# SuperCapacitor_Schmatic_V3.net
KiCad netlist of a schematic drawn in EAGLE
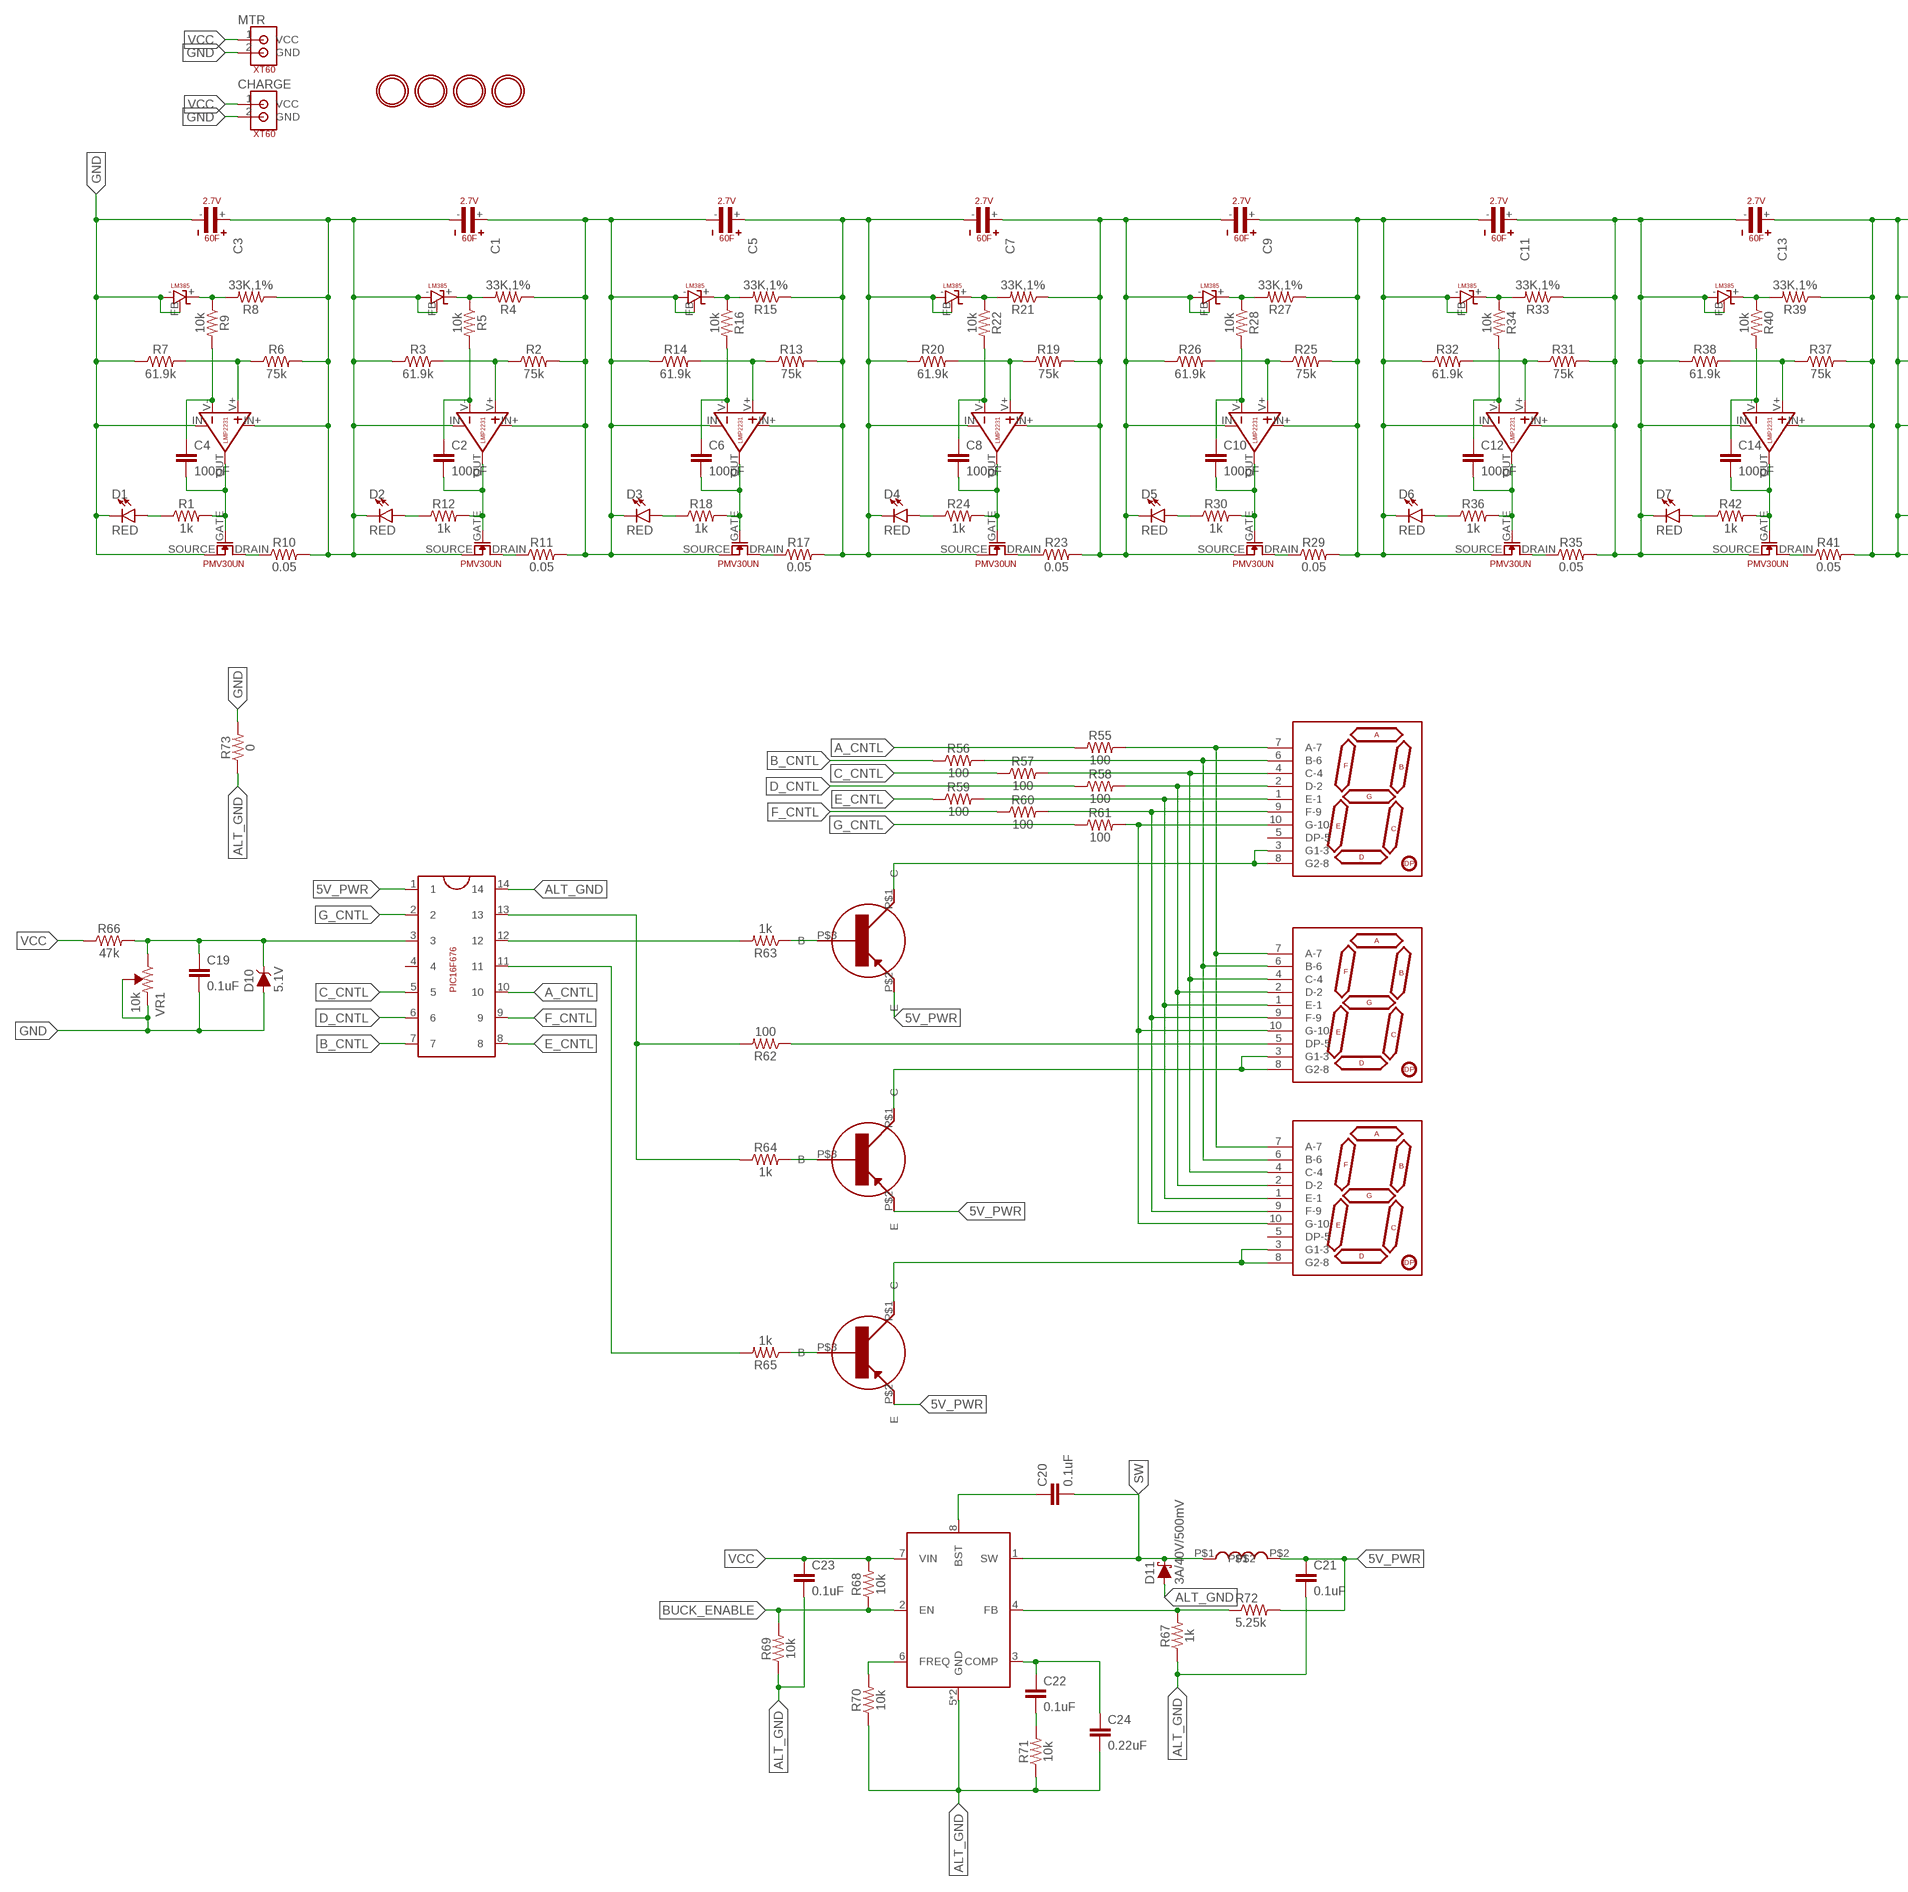
[diagram p0: schematic, sheet 1, part 1 of 2]
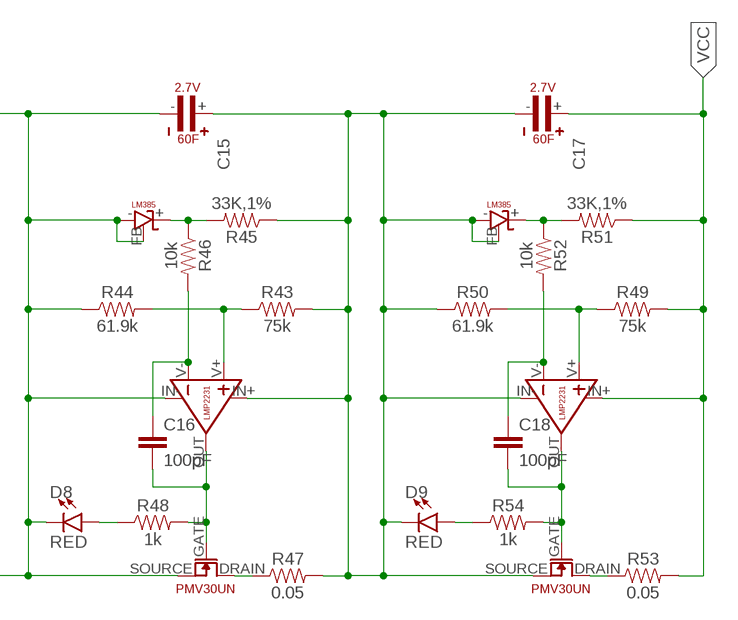
[diagram p1: schematic, sheet 1, part 2 of 2]

(export (version "E")
  (design (tool "Eeschema 10.0.6"))
  (components
    (comp (ref "3.3V_BUCK")
      (value "SOIC8E")
      (footprint "eagle-import:SOIC127P600X170-9N")
      (libsource (lib "eagle-import") (part "SOIC8E"))
    )
    (comp (ref "C1")
      (value "2.7V 60F")
      (footprint "eagle-import:2.7V_60F")
      (libsource (lib "eagle-import") (part "2.7V_60F"))
    )
    (comp (ref "C2")
      (value "100pF")
      (footprint "eagle-import:0603")
      (libsource (lib "eagle-import") (part "100PF-0603-50V-5%"))
    )
    (comp (ref "C3")
      (value "2.7V 60F")
      (footprint "eagle-import:2.7V_60F")
      (libsource (lib "eagle-import") (part "2.7V_60F"))
    )
    (comp (ref "C4")
      (value "100pF")
      (footprint "eagle-import:0603")
      (libsource (lib "eagle-import") (part "100PF-0603-50V-5%"))
    )
    (comp (ref "C5")
      (value "2.7V 60F")
      (footprint "eagle-import:2.7V_60F")
      (libsource (lib "eagle-import") (part "2.7V_60F"))
    )
    (comp (ref "C6")
      (value "100pF")
      (footprint "eagle-import:0603")
      (libsource (lib "eagle-import") (part "100PF-0603-50V-5%"))
    )
    (comp (ref "C7")
      (value "2.7V 60F")
      (footprint "eagle-import:2.7V_60F")
      (libsource (lib "eagle-import") (part "2.7V_60F"))
    )
    (comp (ref "C8")
      (value "100pF")
      (footprint "eagle-import:0603")
      (libsource (lib "eagle-import") (part "100PF-0603-50V-5%"))
    )
    (comp (ref "C9")
      (value "2.7V 60F")
      (footprint "eagle-import:2.7V_60F")
      (libsource (lib "eagle-import") (part "2.7V_60F"))
    )
    (comp (ref "C10")
      (value "100pF")
      (footprint "eagle-import:0603")
      (libsource (lib "eagle-import") (part "100PF-0603-50V-5%"))
    )
    (comp (ref "C11")
      (value "2.7V 60F")
      (footprint "eagle-import:2.7V_60F")
      (libsource (lib "eagle-import") (part "2.7V_60F"))
    )
    (comp (ref "C12")
      (value "100pF")
      (footprint "eagle-import:0603")
      (libsource (lib "eagle-import") (part "100PF-0603-50V-5%"))
    )
    (comp (ref "C13")
      (value "2.7V 60F")
      (footprint "eagle-import:2.7V_60F")
      (libsource (lib "eagle-import") (part "2.7V_60F"))
    )
    (comp (ref "C14")
      (value "100pF")
      (footprint "eagle-import:0603")
      (libsource (lib "eagle-import") (part "100PF-0603-50V-5%"))
    )
    (comp (ref "C15")
      (value "2.7V 60F")
      (footprint "eagle-import:2.7V_60F")
      (libsource (lib "eagle-import") (part "2.7V_60F"))
    )
    (comp (ref "C16")
      (value "100pF")
      (footprint "eagle-import:0603")
      (libsource (lib "eagle-import") (part "100PF-0603-50V-5%"))
    )
    (comp (ref "C17")
      (value "2.7V 60F")
      (footprint "eagle-import:2.7V_60F")
      (libsource (lib "eagle-import") (part "2.7V_60F"))
    )
    (comp (ref "C18")
      (value "100pF")
      (footprint "eagle-import:0603")
      (libsource (lib "eagle-import") (part "100PF-0603-50V-5%"))
    )
    (comp (ref "C19")
      (value "0.1uF")
      (footprint "eagle-import:0603")
      (libsource (lib "eagle-import") (part "SparkFun-Capacitors_510_0.1UF-0603-25V-5%"))
    )
    (comp (ref "C20")
      (value "0.1uF")
      (footprint "eagle-import:0603")
      (libsource (lib "eagle-import") (part "0.1UF-0603-25V-(+80/-20%)"))
    )
    (comp (ref "C21")
      (value "0.1uF")
      (footprint "eagle-import:0603")
      (libsource (lib "eagle-import") (part "0.1UF-0603-25V-(+80/-20%)"))
    )
    (comp (ref "C22")
      (value "0.1uF")
      (footprint "eagle-import:0603")
      (libsource (lib "eagle-import") (part "0.1UF-0603-25V-(+80/-20%)"))
    )
    (comp (ref "C23")
      (value "0.1uF")
      (footprint "eagle-import:0603")
      (libsource (lib "eagle-import") (part "0.1UF-0603-25V-(+80/-20%)"))
    )
    (comp (ref "C24")
      (value "0.22uF")
      (footprint "eagle-import:0603")
      (libsource (lib "eagle-import") (part "0.22UF-0603-50V-(-20/+80%)"))
    )
    (comp (ref "CHARGE")
      (value "XT60_CIRCLE")
      (footprint "eagle-import:XT60_CIRCLE")
      (libsource (lib "eagle-import") (part "XT60_CIRCLE"))
    )
    (comp (ref "D1")
      (value "RED")
      (footprint "eagle-import:LED-0603")
      (libsource (lib "eagle-import") (part "LED-RED0603"))
    )
    (comp (ref "D2")
      (value "RED")
      (footprint "eagle-import:LED-0603")
      (libsource (lib "eagle-import") (part "LED-RED0603"))
    )
    (comp (ref "D3")
      (value "RED")
      (footprint "eagle-import:LED-0603")
      (libsource (lib "eagle-import") (part "LED-RED0603"))
    )
    (comp (ref "D4")
      (value "RED")
      (footprint "eagle-import:LED-0603")
      (libsource (lib "eagle-import") (part "LED-RED0603"))
    )
    (comp (ref "D5")
      (value "RED")
      (footprint "eagle-import:LED-0603")
      (libsource (lib "eagle-import") (part "LED-RED0603"))
    )
    (comp (ref "D6")
      (value "RED")
      (footprint "eagle-import:LED-0603")
      (libsource (lib "eagle-import") (part "LED-RED0603"))
    )
    (comp (ref "D7")
      (value "RED")
      (footprint "eagle-import:LED-0603")
      (libsource (lib "eagle-import") (part "LED-RED0603"))
    )
    (comp (ref "D8")
      (value "RED")
      (footprint "eagle-import:LED-0603")
      (libsource (lib "eagle-import") (part "LED-RED0603"))
    )
    (comp (ref "D9")
      (value "RED")
      (footprint "eagle-import:LED-0603")
      (libsource (lib "eagle-import") (part "LED-RED0603"))
    )
    (comp (ref "D10")
      (value "5.1V")
      (footprint "eagle-import:SOD-323")
      (libsource (lib "eagle-import") (part "DIODE-ZENER-MMSZ5232BS"))
    )
    (comp (ref "D11")
      (value "3A/40V/500mV")
      (footprint "eagle-import:SMA-DIODE")
      (libsource (lib "eagle-import") (part "DIODE-SCHOTTKY-B340A"))
    )
    (comp (ref "MTR")
      (value "XT60_CIRCLE")
      (footprint "eagle-import:XT60_CIRCLE")
      (libsource (lib "eagle-import") (part "XT60_CIRCLE"))
    )
    (comp (ref "R1")
      (value "1k")
      (footprint "eagle-import:0603")
      (libsource (lib "eagle-import") (part "SparkFun-Resistors_532_1KOHM-0603-1/10W-1%"))
    )
    (comp (ref "R2")
      (value "75k")
      (footprint "eagle-import:0603@1")
      (libsource (lib "eagle-import") (part "75KOHM-0603-1/10W-1%"))
    )
    (comp (ref "R3")
      (value "61.9k")
      (footprint "eagle-import:0603@1")
      (libsource (lib "eagle-import") (part "75KOHM-0603-1/10W-1%"))
    )
    (comp (ref "R4")
      (value "33K,1%")
      (footprint "eagle-import:0603@1")
      (libsource (lib "eagle-import") (part "1MOHM-0603-1/4W-5%"))
    )
    (comp (ref "R5")
      (value "10k")
      (footprint "eagle-import:0603")
      (libsource (lib "eagle-import") (part "10KOHM-0603-1/10W-1%"))
    )
    (comp (ref "R6")
      (value "75k")
      (footprint "eagle-import:0603@1")
      (libsource (lib "eagle-import") (part "75KOHM-0603-1/10W-1%"))
    )
    (comp (ref "R7")
      (value "61.9k")
      (footprint "eagle-import:0603@1")
      (libsource (lib "eagle-import") (part "75KOHM-0603-1/10W-1%"))
    )
    (comp (ref "R8")
      (value "33K,1%")
      (footprint "eagle-import:0603@1")
      (libsource (lib "eagle-import") (part "1MOHM-0603-1/4W-5%"))
    )
    (comp (ref "R9")
      (value "10k")
      (footprint "eagle-import:0603")
      (libsource (lib "eagle-import") (part "10KOHM-0603-1/10W-1%"))
    )
    (comp (ref "R10")
      (value "0.05")
      (footprint "eagle-import:2512")
      (libsource (lib "eagle-import") (part "0.05OHM-2512-3W-1%"))
    )
    (comp (ref "R11")
      (value "0.05")
      (footprint "eagle-import:2512")
      (libsource (lib "eagle-import") (part "0.05OHM-2512-3W-1%"))
    )
    (comp (ref "R12")
      (value "1k")
      (footprint "eagle-import:0603")
      (libsource (lib "eagle-import") (part "SparkFun-Resistors_532_1KOHM-0603-1/10W-1%"))
    )
    (comp (ref "R13")
      (value "75k")
      (footprint "eagle-import:0603@1")
      (libsource (lib "eagle-import") (part "75KOHM-0603-1/10W-1%"))
    )
    (comp (ref "R14")
      (value "61.9k")
      (footprint "eagle-import:0603@1")
      (libsource (lib "eagle-import") (part "75KOHM-0603-1/10W-1%"))
    )
    (comp (ref "R15")
      (value "33K,1%")
      (footprint "eagle-import:0603@1")
      (libsource (lib "eagle-import") (part "1MOHM-0603-1/4W-5%"))
    )
    (comp (ref "R16")
      (value "10k")
      (footprint "eagle-import:0603")
      (libsource (lib "eagle-import") (part "10KOHM-0603-1/10W-1%"))
    )
    (comp (ref "R17")
      (value "0.05")
      (footprint "eagle-import:2512")
      (libsource (lib "eagle-import") (part "0.05OHM-2512-3W-1%"))
    )
    (comp (ref "R18")
      (value "1k")
      (footprint "eagle-import:0603")
      (libsource (lib "eagle-import") (part "SparkFun-Resistors_532_1KOHM-0603-1/10W-1%"))
    )
    (comp (ref "R19")
      (value "75k")
      (footprint "eagle-import:0603@1")
      (libsource (lib "eagle-import") (part "75KOHM-0603-1/10W-1%"))
    )
    (comp (ref "R20")
      (value "61.9k")
      (footprint "eagle-import:0603@1")
      (libsource (lib "eagle-import") (part "75KOHM-0603-1/10W-1%"))
    )
    (comp (ref "R21")
      (value "33K,1%")
      (footprint "eagle-import:0603@1")
      (libsource (lib "eagle-import") (part "1MOHM-0603-1/4W-5%"))
    )
    (comp (ref "R22")
      (value "10k")
      (footprint "eagle-import:0603")
      (libsource (lib "eagle-import") (part "10KOHM-0603-1/10W-1%"))
    )
    (comp (ref "R23")
      (value "0.05")
      (footprint "eagle-import:2512")
      (libsource (lib "eagle-import") (part "0.05OHM-2512-3W-1%"))
    )
    (comp (ref "R24")
      (value "1k")
      (footprint "eagle-import:0603")
      (libsource (lib "eagle-import") (part "SparkFun-Resistors_532_1KOHM-0603-1/10W-1%"))
    )
    (comp (ref "R25")
      (value "75k")
      (footprint "eagle-import:0603@1")
      (libsource (lib "eagle-import") (part "75KOHM-0603-1/10W-1%"))
    )
    (comp (ref "R26")
      (value "61.9k")
      (footprint "eagle-import:0603@1")
      (libsource (lib "eagle-import") (part "75KOHM-0603-1/10W-1%"))
    )
    (comp (ref "R27")
      (value "33K,1%")
      (footprint "eagle-import:0603@1")
      (libsource (lib "eagle-import") (part "1MOHM-0603-1/4W-5%"))
    )
    (comp (ref "R28")
      (value "10k")
      (footprint "eagle-import:0603")
      (libsource (lib "eagle-import") (part "10KOHM-0603-1/10W-1%"))
    )
    (comp (ref "R29")
      (value "0.05")
      (footprint "eagle-import:2512")
      (libsource (lib "eagle-import") (part "0.05OHM-2512-3W-1%"))
    )
    (comp (ref "R30")
      (value "1k")
      (footprint "eagle-import:0603")
      (libsource (lib "eagle-import") (part "SparkFun-Resistors_532_1KOHM-0603-1/10W-1%"))
    )
    (comp (ref "R31")
      (value "75k")
      (footprint "eagle-import:0603@1")
      (libsource (lib "eagle-import") (part "75KOHM-0603-1/10W-1%"))
    )
    (comp (ref "R32")
      (value "61.9k")
      (footprint "eagle-import:0603@1")
      (libsource (lib "eagle-import") (part "75KOHM-0603-1/10W-1%"))
    )
    (comp (ref "R33")
      (value "33K,1%")
      (footprint "eagle-import:0603@1")
      (libsource (lib "eagle-import") (part "1MOHM-0603-1/4W-5%"))
    )
    (comp (ref "R34")
      (value "10k")
      (footprint "eagle-import:0603")
      (libsource (lib "eagle-import") (part "10KOHM-0603-1/10W-1%"))
    )
    (comp (ref "R35")
      (value "0.05")
      (footprint "eagle-import:2512")
      (libsource (lib "eagle-import") (part "0.05OHM-2512-3W-1%"))
    )
    (comp (ref "R36")
      (value "1k")
      (footprint "eagle-import:0603")
      (libsource (lib "eagle-import") (part "SparkFun-Resistors_532_1KOHM-0603-1/10W-1%"))
    )
    (comp (ref "R37")
      (value "75k")
      (footprint "eagle-import:0603@1")
      (libsource (lib "eagle-import") (part "75KOHM-0603-1/10W-1%"))
    )
    (comp (ref "R38")
      (value "61.9k")
      (footprint "eagle-import:0603@1")
      (libsource (lib "eagle-import") (part "75KOHM-0603-1/10W-1%"))
    )
    (comp (ref "R39")
      (value "33K,1%")
      (footprint "eagle-import:0603@1")
      (libsource (lib "eagle-import") (part "1MOHM-0603-1/4W-5%"))
    )
    (comp (ref "R40")
      (value "10k")
      (footprint "eagle-import:0603")
      (libsource (lib "eagle-import") (part "10KOHM-0603-1/10W-1%"))
    )
    (comp (ref "R41")
      (value "0.05")
      (footprint "eagle-import:2512")
      (libsource (lib "eagle-import") (part "0.05OHM-2512-3W-1%"))
    )
    (comp (ref "R42")
      (value "1k")
      (footprint "eagle-import:0603")
      (libsource (lib "eagle-import") (part "SparkFun-Resistors_532_1KOHM-0603-1/10W-1%"))
    )
    (comp (ref "R43")
      (value "75k")
      (footprint "eagle-import:0603@1")
      (libsource (lib "eagle-import") (part "75KOHM-0603-1/10W-1%"))
    )
    (comp (ref "R44")
      (value "61.9k")
      (footprint "eagle-import:0603@1")
      (libsource (lib "eagle-import") (part "75KOHM-0603-1/10W-1%"))
    )
    (comp (ref "R45")
      (value "33K,1%")
      (footprint "eagle-import:0603@1")
      (libsource (lib "eagle-import") (part "1MOHM-0603-1/4W-5%"))
    )
    (comp (ref "R46")
      (value "10k")
      (footprint "eagle-import:0603")
      (libsource (lib "eagle-import") (part "10KOHM-0603-1/10W-1%"))
    )
    (comp (ref "R47")
      (value "0.05")
      (footprint "eagle-import:2512")
      (libsource (lib "eagle-import") (part "0.05OHM-2512-3W-1%"))
    )
    (comp (ref "R48")
      (value "1k")
      (footprint "eagle-import:0603")
      (libsource (lib "eagle-import") (part "SparkFun-Resistors_532_1KOHM-0603-1/10W-1%"))
    )
    (comp (ref "R49")
      (value "75k")
      (footprint "eagle-import:0603@1")
      (libsource (lib "eagle-import") (part "75KOHM-0603-1/10W-1%"))
    )
    (comp (ref "R50")
      (value "61.9k")
      (footprint "eagle-import:0603@1")
      (libsource (lib "eagle-import") (part "75KOHM-0603-1/10W-1%"))
    )
    (comp (ref "R51")
      (value "33K,1%")
      (footprint "eagle-import:0603@1")
      (libsource (lib "eagle-import") (part "1MOHM-0603-1/4W-5%"))
    )
    (comp (ref "R52")
      (value "10k")
      (footprint "eagle-import:0603")
      (libsource (lib "eagle-import") (part "10KOHM-0603-1/10W-1%"))
    )
    (comp (ref "R53")
      (value "0.05")
      (footprint "eagle-import:2512")
      (libsource (lib "eagle-import") (part "0.05OHM-2512-3W-1%"))
    )
    (comp (ref "R54")
      (value "1k")
      (footprint "eagle-import:0603")
      (libsource (lib "eagle-import") (part "SparkFun-Resistors_532_1KOHM-0603-1/10W-1%"))
    )
    (comp (ref "R55")
      (value "100")
      (footprint "eagle-import:0603")
      (libsource (lib "eagle-import") (part "100OHM-0603-1/4W-5%"))
    )
    (comp (ref "R56")
      (value "100")
      (footprint "eagle-import:0603")
      (libsource (lib "eagle-import") (part "100OHM-0603-1/4W-5%"))
    )
    (comp (ref "R57")
      (value "100")
      (footprint "eagle-import:0603")
      (libsource (lib "eagle-import") (part "100OHM-0603-1/4W-5%"))
    )
    (comp (ref "R58")
      (value "100")
      (footprint "eagle-import:0603")
      (libsource (lib "eagle-import") (part "100OHM-0603-1/4W-5%"))
    )
    (comp (ref "R59")
      (value "100")
      (footprint "eagle-import:0603")
      (libsource (lib "eagle-import") (part "100OHM-0603-1/4W-5%"))
    )
    (comp (ref "R60")
      (value "100")
      (footprint "eagle-import:0603")
      (libsource (lib "eagle-import") (part "100OHM-0603-1/4W-5%"))
    )
    (comp (ref "R61")
      (value "100")
      (footprint "eagle-import:0603")
      (libsource (lib "eagle-import") (part "100OHM-0603-1/4W-5%"))
    )
    (comp (ref "R62")
      (value "100")
      (footprint "eagle-import:0603")
      (libsource (lib "eagle-import") (part "100OHM-0603-1/4W-5%"))
    )
    (comp (ref "R63")
      (value "1k")
      (footprint "eagle-import:0603")
      (libsource (lib "eagle-import") (part "SparkFun-Resistors_532_1KOHM-0603-1/10W-1%"))
    )
    (comp (ref "R64")
      (value "1k")
      (footprint "eagle-import:0603")
      (libsource (lib "eagle-import") (part "SparkFun-Resistors_532_1KOHM-0603-1/10W-1%"))
    )
    (comp (ref "R65")
      (value "1k")
      (footprint "eagle-import:0603")
      (libsource (lib "eagle-import") (part "SparkFun-Resistors_532_1KOHM-0603-1/10W-1%"))
    )
    (comp (ref "R66")
      (value "47k")
      (footprint "eagle-import:0603")
      (libsource (lib "eagle-import") (part "47KOHM-0603-1/10W-1%"))
    )
    (comp (ref "R67")
      (value "1k")
      (footprint "eagle-import:0603")
      (libsource (lib "eagle-import") (part "1KOHM-0603-1/10W-1%"))
    )
    (comp (ref "R68")
      (value "10k")
      (footprint "eagle-import:0603")
      (libsource (lib "eagle-import") (part "10KOHM-0603-1/10W-1%"))
    )
    (comp (ref "R69")
      (value "10k")
      (footprint "eagle-import:0603")
      (libsource (lib "eagle-import") (part "10KOHM-0603-1/10W-1%"))
    )
    (comp (ref "R70")
      (value "10k")
      (footprint "eagle-import:0603")
      (libsource (lib "eagle-import") (part "10KOHM-0603-1/10W-1%"))
    )
    (comp (ref "R71")
      (value "10k")
      (footprint "eagle-import:0603")
      (libsource (lib "eagle-import") (part "10KOHM-0603-1/10W-1%"))
    )
    (comp (ref "R72")
      (value "5.25k")
      (footprint "eagle-import:RES_0805")
      (fields
        (field (name "DIGIKEY_PART_NUMBER") "541-0.0ATR-ND")
        (field (name "MANUFACTURER") "Vishay Dale")
        (field (name "MPN") "CRCW08050000Z0EA")
        (field (name "CREATED_BY") "PCBLayout.com")
      )
      (libsource (lib "eagle-import") (part "CRCW08050000Z0EA"))
    )
    (comp (ref "R73")
      (value "0")
      (footprint "eagle-import:0603")
      (libsource (lib "eagle-import") (part "0OHM-0603-1/10W-5%"))
    )
    (comp (ref "U$1")
      (value "LMP2231")
      (footprint "eagle-import:LMP2231_SOT23_5")
      (libsource (lib "eagle-import") (part "LMP2231"))
    )
    (comp (ref "U$2")
      (value "LM385")
      (footprint "eagle-import:LM385_SOT23")
      (libsource (lib "eagle-import") (part "LM385"))
    )
    (comp (ref "U$3")
      (value "PMV30UN_MOS")
      (footprint "eagle-import:PMV30UN_SOT23")
      (libsource (lib "eagle-import") (part "PMV30UN_MOS"))
    )
    (comp (ref "U$4")
      (value "LMP2231")
      (footprint "eagle-import:LMP2231_SOT23_5")
      (libsource (lib "eagle-import") (part "LMP2231"))
    )
    (comp (ref "U$5")
      (value "LM385")
      (footprint "eagle-import:LM385_SOT23")
      (libsource (lib "eagle-import") (part "LM385"))
    )
    (comp (ref "U$6")
      (value "PMV30UN_MOS")
      (footprint "eagle-import:PMV30UN_SOT23")
      (libsource (lib "eagle-import") (part "PMV30UN_MOS"))
    )
    (comp (ref "U$7")
      (value "LMP2231")
      (footprint "eagle-import:LMP2231_SOT23_5")
      (libsource (lib "eagle-import") (part "LMP2231"))
    )
    (comp (ref "U$8")
      (value "LM385")
      (footprint "eagle-import:LM385_SOT23")
      (libsource (lib "eagle-import") (part "LM385"))
    )
    (comp (ref "U$9")
      (value "PMV30UN_MOS")
      (footprint "eagle-import:PMV30UN_SOT23")
      (libsource (lib "eagle-import") (part "PMV30UN_MOS"))
    )
    (comp (ref "U$10")
      (value "LMP2231")
      (footprint "eagle-import:LMP2231_SOT23_5")
      (libsource (lib "eagle-import") (part "LMP2231"))
    )
    (comp (ref "U$11")
      (value "LM385")
      (footprint "eagle-import:LM385_SOT23")
      (libsource (lib "eagle-import") (part "LM385"))
    )
    (comp (ref "U$12")
      (value "PMV30UN_MOS")
      (footprint "eagle-import:PMV30UN_SOT23")
      (libsource (lib "eagle-import") (part "PMV30UN_MOS"))
    )
    (comp (ref "U$13")
      (value "LMP2231")
      (footprint "eagle-import:LMP2231_SOT23_5")
      (libsource (lib "eagle-import") (part "LMP2231"))
    )
    (comp (ref "U$14")
      (value "LM385")
      (footprint "eagle-import:LM385_SOT23")
      (libsource (lib "eagle-import") (part "LM385"))
    )
    (comp (ref "U$15")
      (value "PMV30UN_MOS")
      (footprint "eagle-import:PMV30UN_SOT23")
      (libsource (lib "eagle-import") (part "PMV30UN_MOS"))
    )
    (comp (ref "U$16")
      (value "LMP2231")
      (footprint "eagle-import:LMP2231_SOT23_5")
      (libsource (lib "eagle-import") (part "LMP2231"))
    )
    (comp (ref "U$17")
      (value "LM385")
      (footprint "eagle-import:LM385_SOT23")
      (libsource (lib "eagle-import") (part "LM385"))
    )
    (comp (ref "U$18")
      (value "PMV30UN_MOS")
      (footprint "eagle-import:PMV30UN_SOT23")
      (libsource (lib "eagle-import") (part "PMV30UN_MOS"))
    )
    (comp (ref "U$19")
      (value "LMP2231")
      (footprint "eagle-import:LMP2231_SOT23_5")
      (libsource (lib "eagle-import") (part "LMP2231"))
    )
    (comp (ref "U$20")
      (value "LM385")
      (footprint "eagle-import:LM385_SOT23")
      (libsource (lib "eagle-import") (part "LM385"))
    )
    (comp (ref "U$21")
      (value "PMV30UN_MOS")
      (footprint "eagle-import:PMV30UN_SOT23")
      (libsource (lib "eagle-import") (part "PMV30UN_MOS"))
    )
    (comp (ref "U$22")
      (value "LMP2231")
      (footprint "eagle-import:LMP2231_SOT23_5")
      (libsource (lib "eagle-import") (part "LMP2231"))
    )
    (comp (ref "U$23")
      (value "LM385")
      (footprint "eagle-import:LM385_SOT23")
      (libsource (lib "eagle-import") (part "LM385"))
    )
    (comp (ref "U$24")
      (value "PMV30UN_MOS")
      (footprint "eagle-import:PMV30UN_SOT23")
      (libsource (lib "eagle-import") (part "PMV30UN_MOS"))
    )
    (comp (ref "U$25")
      (value "LMP2231")
      (footprint "eagle-import:LMP2231_SOT23_5")
      (libsource (lib "eagle-import") (part "LMP2231"))
    )
    (comp (ref "U$26")
      (value "LM385")
      (footprint "eagle-import:LM385_SOT23")
      (libsource (lib "eagle-import") (part "LM385"))
    )
    (comp (ref "U$27")
      (value "PMV30UN_MOS")
      (footprint "eagle-import:PMV30UN_SOT23")
      (libsource (lib "eagle-import") (part "PMV30UN_MOS"))
    )
    (comp (ref "U$30")
      (value "M5")
      (footprint "eagle-import:M5")
      (libsource (lib "eagle-import") (part "M5"))
    )
    (comp (ref "U$31")
      (value "M5")
      (footprint "eagle-import:M5")
      (libsource (lib "eagle-import") (part "M5"))
    )
    (comp (ref "U$32")
      (value "M5")
      (footprint "eagle-import:M5")
      (libsource (lib "eagle-import") (part "M5"))
    )
    (comp (ref "U$33")
      (value "M5")
      (footprint "eagle-import:M5")
      (libsource (lib "eagle-import") (part "M5"))
    )
    (comp (ref "U$35")
      (value "DSM7T")
      (footprint "eagle-import:7-SEGMENT_SMD")
      (libsource (lib "eagle-import") (part "DSM7T"))
    )
    (comp (ref "U$36")
      (value "DSM7T")
      (footprint "eagle-import:7-SEGMENT_SMD")
      (libsource (lib "eagle-import") (part "DSM7T"))
    )
    (comp (ref "U$37")
      (value "DSM7T")
      (footprint "eagle-import:7-SEGMENT_SMD")
      (libsource (lib "eagle-import") (part "DSM7T"))
    )
    (comp (ref "U$38")
      (value "PIC16F676")
      (footprint "eagle-import:PIC16F676")
      (libsource (lib "eagle-import") (part "PIC16F676"))
    )
    (comp (ref "U$39")
      (value "4.7UH_INDUCTOR")
      (footprint "eagle-import:4.7UH_INDUCTOR")
      (libsource (lib "eagle-import") (part "4.7UH_INDUCTOR"))
    )
    (comp (ref "U$40")
      (value "SOT_223")
      (footprint "eagle-import:BC856BMB")
      (libsource (lib "eagle-import") (part "SOT_223"))
    )
    (comp (ref "U$41")
      (value "SOT_223")
      (footprint "eagle-import:BC856BMB")
      (libsource (lib "eagle-import") (part "SOT_223"))
    )
    (comp (ref "U$42")
      (value "SOT_223")
      (footprint "eagle-import:BC856BMB")
      (libsource (lib "eagle-import") (part "SOT_223"))
    )
    (comp (ref "VR1")
      (value "10k")
      (footprint "eagle-import:TRIMPOT-SMD-TC33X")
      (libsource (lib "eagle-import") (part "TRIMPOT-SMD-3MM-OPEN-1/10W-25%"))
    )
  )
  (nets
    (net (code "1") (name "5V_PWR") (class "Default")
      (node (ref "C21") (pin "1") (pinfunction "1_1") (pintype "passive"))
      (node (ref "R72") (pin "2") (pinfunction "2_2") (pintype "passive"))
      (node (ref "U$38") (pin "1") (pinfunction "1_1") (pintype "bidirectional"))
      (node (ref "U$39") (pin "P$2") (pinfunction "P$2_P$2") (pintype "bidirectional"))
      (node (ref "U$40") (pin "P$2") (pinfunction "E_P$2") (pintype "bidirectional"))
      (node (ref "U$41") (pin "P$2") (pinfunction "E_P$2") (pintype "bidirectional"))
      (node (ref "U$42") (pin "P$2") (pinfunction "E_P$2") (pintype "bidirectional"))
    )
    (net (code "2") (name "ALT_GND") (class "Default")
      (node (ref "3.3V_BUCK") (pin "5") (pinfunction "GND_5") (pintype "bidirectional"))
      (node (ref "3.3V_BUCK") (pin "9") (pinfunction "GND_9") (pintype "bidirectional"))
      (node (ref "C21") (pin "2") (pinfunction "2_2") (pintype "passive"))
      (node (ref "C23") (pin "2") (pinfunction "2_2") (pintype "passive"))
      (node (ref "C24") (pin "2") (pinfunction "2_2") (pintype "passive"))
      (node (ref "D11") (pin "A") (pinfunction "A_A") (pintype "passive"))
      (node (ref "R67") (pin "1") (pinfunction "1_1") (pintype "passive"))
      (node (ref "R69") (pin "1") (pinfunction "1_1") (pintype "passive"))
      (node (ref "R70") (pin "1") (pinfunction "1_1") (pintype "passive"))
      (node (ref "R71") (pin "1") (pinfunction "1_1") (pintype "passive"))
      (node (ref "R73") (pin "1") (pinfunction "1_1") (pintype "passive"))
      (node (ref "U$38") (pin "14") (pinfunction "14_14") (pintype "bidirectional"))
    )
    (net (code "3") (name "A_CNTL") (class "Default")
      (node (ref "R55") (pin "1") (pinfunction "1_1") (pintype "passive"))
      (node (ref "U$38") (pin "10") (pinfunction "10_10") (pintype "bidirectional"))
    )
    (net (code "4") (name "BUCK_ENABLE") (class "Default")
      (node (ref "3.3V_BUCK") (pin "2") (pinfunction "EN_2") (pintype "bidirectional"))
      (node (ref "R68") (pin "1") (pinfunction "1_1") (pintype "passive"))
      (node (ref "R69") (pin "2") (pinfunction "2_2") (pintype "passive"))
    )
    (net (code "5") (name "B_CNTL") (class "Default")
      (node (ref "R56") (pin "1") (pinfunction "1_1") (pintype "passive"))
      (node (ref "U$38") (pin "7") (pinfunction "7_7") (pintype "bidirectional"))
    )
    (net (code "6") (name "C_CNTL") (class "Default")
      (node (ref "R57") (pin "1") (pinfunction "1_1") (pintype "passive"))
      (node (ref "U$38") (pin "5") (pinfunction "5_5") (pintype "bidirectional"))
    )
    (net (code "7") (name "D_CNTL") (class "Default")
      (node (ref "R58") (pin "1") (pinfunction "1_1") (pintype "passive"))
      (node (ref "U$38") (pin "6") (pinfunction "6_6") (pintype "bidirectional"))
    )
    (net (code "8") (name "E_CNTL") (class "Default")
      (node (ref "R59") (pin "1") (pinfunction "1_1") (pintype "passive"))
      (node (ref "U$38") (pin "8") (pinfunction "8_8") (pintype "bidirectional"))
    )
    (net (code "9") (name "F_CNTL") (class "Default")
      (node (ref "R60") (pin "1") (pinfunction "1_1") (pintype "passive"))
      (node (ref "U$38") (pin "9") (pinfunction "9_9") (pintype "bidirectional"))
    )
    (net (code "10") (name "GND") (class "Default")
      (node (ref "C19") (pin "2") (pinfunction "2_2") (pintype "passive"))
      (node (ref "C3") (pin "-") (pinfunction "-_-") (pintype "bidirectional"))
      (node (ref "CHARGE") (pin "2") (pinfunction "GND_2") (pintype "bidirectional"))
      (node (ref "D1") (pin "C") (pinfunction "C_C") (pintype "passive"))
      (node (ref "D10") (pin "A") (pinfunction "A_A") (pintype "passive"))
      (node (ref "MTR") (pin "2") (pinfunction "GND_2") (pintype "bidirectional"))
      (node (ref "R7") (pin "1") (pinfunction "1_1") (pintype "passive"))
      (node (ref "R73") (pin "2") (pinfunction "2_2") (pintype "passive"))
      (node (ref "U$4") (pin "IN-") (pinfunction "IN-_IN-") (pintype "bidirectional"))
      (node (ref "U$5") (pin "-") (pinfunction "-_-") (pintype "bidirectional"))
      (node (ref "U$5") (pin "FB") (pinfunction "FB_FB") (pintype "bidirectional"))
      (node (ref "U$6") (pin "SOURCE") (pinfunction "SOURCE_SOURCE") (pintype "bidirectional"))
      (node (ref "VR1") (pin "2") (pinfunction "WIPER_2") (pintype "passive"))
      (node (ref "VR1") (pin "3") (pinfunction "CCW_3") (pintype "passive"))
    )
    (net (code "11") (name "G_CNTL") (class "Default")
      (node (ref "R61") (pin "1") (pinfunction "1_1") (pintype "passive"))
      (node (ref "U$38") (pin "2") (pinfunction "2_2") (pintype "bidirectional"))
    )
    (net (code "12") (name "Net-(3.3V_BUCK-BST)") (class "Default")
      (node (ref "3.3V_BUCK") (pin "8") (pinfunction "BST_8") (pintype "bidirectional"))
      (node (ref "C20") (pin "1") (pinfunction "1_1") (pintype "passive"))
    )
    (net (code "13") (name "Net-(3.3V_BUCK-COMP)") (class "Default")
      (node (ref "3.3V_BUCK") (pin "3") (pinfunction "COMP_3") (pintype "bidirectional"))
      (node (ref "C22") (pin "1") (pinfunction "1_1") (pintype "passive"))
      (node (ref "C24") (pin "1") (pinfunction "1_1") (pintype "passive"))
    )
    (net (code "14") (name "Net-(3.3V_BUCK-FB)") (class "Default")
      (node (ref "3.3V_BUCK") (pin "4") (pinfunction "FB_4") (pintype "bidirectional"))
      (node (ref "R67") (pin "2") (pinfunction "2_2") (pintype "passive"))
      (node (ref "R72") (pin "1") (pinfunction "1_1") (pintype "passive"))
    )
    (net (code "15") (name "Net-(3.3V_BUCK-FREQ)") (class "Default")
      (node (ref "3.3V_BUCK") (pin "6") (pinfunction "FREQ_6") (pintype "bidirectional"))
      (node (ref "R70") (pin "2") (pinfunction "2_2") (pintype "passive"))
    )
    (net (code "16") (name "Net-(C2-Pad1)") (class "Default")
      (node (ref "C2") (pin "1") (pinfunction "1_1") (pintype "passive"))
      (node (ref "R5") (pin "2") (pinfunction "2_2") (pintype "passive"))
      (node (ref "U$1") (pin "V-") (pinfunction "V-_V-") (pintype "bidirectional"))
    )
    (net (code "17") (name "Net-(C2-Pad2)") (class "Default")
      (node (ref "C2") (pin "2") (pinfunction "2_2") (pintype "passive"))
      (node (ref "R12") (pin "2") (pinfunction "2_2") (pintype "passive"))
      (node (ref "U$1") (pin "OUT") (pinfunction "OUT_OUT") (pintype "bidirectional"))
      (node (ref "U$3") (pin "GATE") (pinfunction "GATE_GATE") (pintype "bidirectional"))
    )
    (net (code "18") (name "Net-(C4-Pad1)") (class "Default")
      (node (ref "C4") (pin "1") (pinfunction "1_1") (pintype "passive"))
      (node (ref "R9") (pin "2") (pinfunction "2_2") (pintype "passive"))
      (node (ref "U$4") (pin "V-") (pinfunction "V-_V-") (pintype "bidirectional"))
    )
    (net (code "19") (name "Net-(C4-Pad2)") (class "Default")
      (node (ref "C4") (pin "2") (pinfunction "2_2") (pintype "passive"))
      (node (ref "R1") (pin "2") (pinfunction "2_2") (pintype "passive"))
      (node (ref "U$4") (pin "OUT") (pinfunction "OUT_OUT") (pintype "bidirectional"))
      (node (ref "U$6") (pin "GATE") (pinfunction "GATE_GATE") (pintype "bidirectional"))
    )
    (net (code "20") (name "Net-(C6-Pad1)") (class "Default")
      (node (ref "C6") (pin "1") (pinfunction "1_1") (pintype "passive"))
      (node (ref "R16") (pin "2") (pinfunction "2_2") (pintype "passive"))
      (node (ref "U$7") (pin "V-") (pinfunction "V-_V-") (pintype "bidirectional"))
    )
    (net (code "21") (name "Net-(C6-Pad2)") (class "Default")
      (node (ref "C6") (pin "2") (pinfunction "2_2") (pintype "passive"))
      (node (ref "R18") (pin "2") (pinfunction "2_2") (pintype "passive"))
      (node (ref "U$7") (pin "OUT") (pinfunction "OUT_OUT") (pintype "bidirectional"))
      (node (ref "U$9") (pin "GATE") (pinfunction "GATE_GATE") (pintype "bidirectional"))
    )
    (net (code "22") (name "Net-(C8-Pad1)") (class "Default")
      (node (ref "C8") (pin "1") (pinfunction "1_1") (pintype "passive"))
      (node (ref "R22") (pin "2") (pinfunction "2_2") (pintype "passive"))
      (node (ref "U$10") (pin "V-") (pinfunction "V-_V-") (pintype "bidirectional"))
    )
    (net (code "23") (name "Net-(C8-Pad2)") (class "Default")
      (node (ref "C8") (pin "2") (pinfunction "2_2") (pintype "passive"))
      (node (ref "R24") (pin "2") (pinfunction "2_2") (pintype "passive"))
      (node (ref "U$10") (pin "OUT") (pinfunction "OUT_OUT") (pintype "bidirectional"))
      (node (ref "U$12") (pin "GATE") (pinfunction "GATE_GATE") (pintype "bidirectional"))
    )
    (net (code "24") (name "Net-(C10-Pad1)") (class "Default")
      (node (ref "C10") (pin "1") (pinfunction "1_1") (pintype "passive"))
      (node (ref "R28") (pin "2") (pinfunction "2_2") (pintype "passive"))
      (node (ref "U$13") (pin "V-") (pinfunction "V-_V-") (pintype "bidirectional"))
    )
    (net (code "25") (name "Net-(C10-Pad2)") (class "Default")
      (node (ref "C10") (pin "2") (pinfunction "2_2") (pintype "passive"))
      (node (ref "R30") (pin "2") (pinfunction "2_2") (pintype "passive"))
      (node (ref "U$13") (pin "OUT") (pinfunction "OUT_OUT") (pintype "bidirectional"))
      (node (ref "U$15") (pin "GATE") (pinfunction "GATE_GATE") (pintype "bidirectional"))
    )
    (net (code "26") (name "Net-(C12-Pad1)") (class "Default")
      (node (ref "C12") (pin "1") (pinfunction "1_1") (pintype "passive"))
      (node (ref "R34") (pin "2") (pinfunction "2_2") (pintype "passive"))
      (node (ref "U$16") (pin "V-") (pinfunction "V-_V-") (pintype "bidirectional"))
    )
    (net (code "27") (name "Net-(C12-Pad2)") (class "Default")
      (node (ref "C12") (pin "2") (pinfunction "2_2") (pintype "passive"))
      (node (ref "R36") (pin "2") (pinfunction "2_2") (pintype "passive"))
      (node (ref "U$16") (pin "OUT") (pinfunction "OUT_OUT") (pintype "bidirectional"))
      (node (ref "U$18") (pin "GATE") (pinfunction "GATE_GATE") (pintype "bidirectional"))
    )
    (net (code "28") (name "Net-(C14-Pad1)") (class "Default")
      (node (ref "C14") (pin "1") (pinfunction "1_1") (pintype "passive"))
      (node (ref "R40") (pin "2") (pinfunction "2_2") (pintype "passive"))
      (node (ref "U$19") (pin "V-") (pinfunction "V-_V-") (pintype "bidirectional"))
    )
    (net (code "29") (name "Net-(C14-Pad2)") (class "Default")
      (node (ref "C14") (pin "2") (pinfunction "2_2") (pintype "passive"))
      (node (ref "R42") (pin "2") (pinfunction "2_2") (pintype "passive"))
      (node (ref "U$19") (pin "OUT") (pinfunction "OUT_OUT") (pintype "bidirectional"))
      (node (ref "U$21") (pin "GATE") (pinfunction "GATE_GATE") (pintype "bidirectional"))
    )
    (net (code "30") (name "Net-(C16-Pad1)") (class "Default")
      (node (ref "C16") (pin "1") (pinfunction "1_1") (pintype "passive"))
      (node (ref "R46") (pin "2") (pinfunction "2_2") (pintype "passive"))
      (node (ref "U$22") (pin "V-") (pinfunction "V-_V-") (pintype "bidirectional"))
    )
    (net (code "31") (name "Net-(C16-Pad2)") (class "Default")
      (node (ref "C16") (pin "2") (pinfunction "2_2") (pintype "passive"))
      (node (ref "R48") (pin "2") (pinfunction "2_2") (pintype "passive"))
      (node (ref "U$22") (pin "OUT") (pinfunction "OUT_OUT") (pintype "bidirectional"))
      (node (ref "U$24") (pin "GATE") (pinfunction "GATE_GATE") (pintype "bidirectional"))
    )
    (net (code "32") (name "Net-(C18-Pad1)") (class "Default")
      (node (ref "C18") (pin "1") (pinfunction "1_1") (pintype "passive"))
      (node (ref "R52") (pin "2") (pinfunction "2_2") (pintype "passive"))
      (node (ref "U$25") (pin "V-") (pinfunction "V-_V-") (pintype "bidirectional"))
    )
    (net (code "33") (name "Net-(C18-Pad2)") (class "Default")
      (node (ref "C18") (pin "2") (pinfunction "2_2") (pintype "passive"))
      (node (ref "R54") (pin "2") (pinfunction "2_2") (pintype "passive"))
      (node (ref "U$25") (pin "OUT") (pinfunction "OUT_OUT") (pintype "bidirectional"))
      (node (ref "U$27") (pin "GATE") (pinfunction "GATE_GATE") (pintype "bidirectional"))
    )
    (net (code "34") (name "Net-(C22-Pad2)") (class "Default")
      (node (ref "C22") (pin "2") (pinfunction "2_2") (pintype "passive"))
      (node (ref "R71") (pin "2") (pinfunction "2_2") (pintype "passive"))
    )
    (net (code "35") (name "Net-(D1-PadA)") (class "Default")
      (node (ref "D1") (pin "A") (pinfunction "A_A") (pintype "passive"))
      (node (ref "R1") (pin "1") (pinfunction "1_1") (pintype "passive"))
    )
    (net (code "36") (name "Net-(D2-PadA)") (class "Default")
      (node (ref "D2") (pin "A") (pinfunction "A_A") (pintype "passive"))
      (node (ref "R12") (pin "1") (pinfunction "1_1") (pintype "passive"))
    )
    (net (code "37") (name "Net-(D3-PadA)") (class "Default")
      (node (ref "D3") (pin "A") (pinfunction "A_A") (pintype "passive"))
      (node (ref "R18") (pin "1") (pinfunction "1_1") (pintype "passive"))
    )
    (net (code "38") (name "Net-(D4-PadA)") (class "Default")
      (node (ref "D4") (pin "A") (pinfunction "A_A") (pintype "passive"))
      (node (ref "R24") (pin "1") (pinfunction "1_1") (pintype "passive"))
    )
    (net (code "39") (name "Net-(D5-PadA)") (class "Default")
      (node (ref "D5") (pin "A") (pinfunction "A_A") (pintype "passive"))
      (node (ref "R30") (pin "1") (pinfunction "1_1") (pintype "passive"))
    )
    (net (code "40") (name "Net-(D6-PadA)") (class "Default")
      (node (ref "D6") (pin "A") (pinfunction "A_A") (pintype "passive"))
      (node (ref "R36") (pin "1") (pinfunction "1_1") (pintype "passive"))
    )
    (net (code "41") (name "Net-(D7-PadA)") (class "Default")
      (node (ref "D7") (pin "A") (pinfunction "A_A") (pintype "passive"))
      (node (ref "R42") (pin "1") (pinfunction "1_1") (pintype "passive"))
    )
    (net (code "42") (name "Net-(D8-PadA)") (class "Default")
      (node (ref "D8") (pin "A") (pinfunction "A_A") (pintype "passive"))
      (node (ref "R48") (pin "1") (pinfunction "1_1") (pintype "passive"))
    )
    (net (code "43") (name "Net-(D9-PadA)") (class "Default")
      (node (ref "D9") (pin "A") (pinfunction "A_A") (pintype "passive"))
      (node (ref "R54") (pin "1") (pinfunction "1_1") (pintype "passive"))
    )
    (net (code "44") (name "Net-(R2-Pad1)") (class "Default")
      (node (ref "R2") (pin "1") (pinfunction "1_1") (pintype "passive"))
      (node (ref "R3") (pin "2") (pinfunction "2_2") (pintype "passive"))
      (node (ref "U$1") (pin "V+") (pinfunction "V+_V+") (pintype "bidirectional"))
    )
    (net (code "45") (name "Net-(R4-Pad2)") (class "Default")
      (node (ref "R4") (pin "2") (pinfunction "2_2") (pintype "passive"))
      (node (ref "R5") (pin "1") (pinfunction "1_1") (pintype "passive"))
      (node (ref "U$2") (pin "+") (pinfunction "+_+") (pintype "bidirectional"))
    )
    (net (code "46") (name "Net-(R6-Pad1)") (class "Default")
      (node (ref "R6") (pin "1") (pinfunction "1_1") (pintype "passive"))
      (node (ref "R7") (pin "2") (pinfunction "2_2") (pintype "passive"))
      (node (ref "U$4") (pin "V+") (pinfunction "V+_V+") (pintype "bidirectional"))
    )
    (net (code "47") (name "Net-(R8-Pad2)") (class "Default")
      (node (ref "R8") (pin "2") (pinfunction "2_2") (pintype "passive"))
      (node (ref "R9") (pin "1") (pinfunction "1_1") (pintype "passive"))
      (node (ref "U$5") (pin "+") (pinfunction "+_+") (pintype "bidirectional"))
    )
    (net (code "48") (name "Net-(R10-1)") (class "Default")
      (node (ref "R10") (pin "P$1") (pinfunction "1_P$1") (pintype "passive"))
      (node (ref "U$6") (pin "DRAIN") (pinfunction "DRAIN_DRAIN") (pintype "bidirectional"))
    )
    (net (code "49") (name "Net-(R10-2)") (class "Default")
      (node (ref "C1") (pin "-") (pinfunction "-_-") (pintype "bidirectional"))
      (node (ref "C3") (pin "+") (pinfunction "+_+") (pintype "bidirectional"))
      (node (ref "D2") (pin "C") (pinfunction "C_C") (pintype "passive"))
      (node (ref "R10") (pin "P$2") (pinfunction "2_P$2") (pintype "passive"))
      (node (ref "R3") (pin "1") (pinfunction "1_1") (pintype "passive"))
      (node (ref "R6") (pin "2") (pinfunction "2_2") (pintype "passive"))
      (node (ref "R8") (pin "1") (pinfunction "1_1") (pintype "passive"))
      (node (ref "U$1") (pin "IN-") (pinfunction "IN-_IN-") (pintype "bidirectional"))
      (node (ref "U$2") (pin "-") (pinfunction "-_-") (pintype "bidirectional"))
      (node (ref "U$2") (pin "FB") (pinfunction "FB_FB") (pintype "bidirectional"))
      (node (ref "U$3") (pin "SOURCE") (pinfunction "SOURCE_SOURCE") (pintype "bidirectional"))
      (node (ref "U$4") (pin "IN+") (pinfunction "IN+_IN+") (pintype "bidirectional"))
    )
    (net (code "50") (name "Net-(R11-1)") (class "Default")
      (node (ref "R11") (pin "P$1") (pinfunction "1_P$1") (pintype "passive"))
      (node (ref "U$3") (pin "DRAIN") (pinfunction "DRAIN_DRAIN") (pintype "bidirectional"))
    )
    (net (code "51") (name "Net-(R11-2)") (class "Default")
      (node (ref "C1") (pin "+") (pinfunction "+_+") (pintype "bidirectional"))
      (node (ref "C5") (pin "-") (pinfunction "-_-") (pintype "bidirectional"))
      (node (ref "D3") (pin "C") (pinfunction "C_C") (pintype "passive"))
      (node (ref "R11") (pin "P$2") (pinfunction "2_P$2") (pintype "passive"))
      (node (ref "R14") (pin "1") (pinfunction "1_1") (pintype "passive"))
      (node (ref "R2") (pin "2") (pinfunction "2_2") (pintype "passive"))
      (node (ref "R4") (pin "1") (pinfunction "1_1") (pintype "passive"))
      (node (ref "U$1") (pin "IN+") (pinfunction "IN+_IN+") (pintype "bidirectional"))
      (node (ref "U$7") (pin "IN-") (pinfunction "IN-_IN-") (pintype "bidirectional"))
      (node (ref "U$8") (pin "-") (pinfunction "-_-") (pintype "bidirectional"))
      (node (ref "U$8") (pin "FB") (pinfunction "FB_FB") (pintype "bidirectional"))
      (node (ref "U$9") (pin "SOURCE") (pinfunction "SOURCE_SOURCE") (pintype "bidirectional"))
    )
    (net (code "52") (name "Net-(R13-Pad1)") (class "Default")
      (node (ref "R13") (pin "1") (pinfunction "1_1") (pintype "passive"))
      (node (ref "R14") (pin "2") (pinfunction "2_2") (pintype "passive"))
      (node (ref "U$7") (pin "V+") (pinfunction "V+_V+") (pintype "bidirectional"))
    )
    (net (code "53") (name "Net-(R15-Pad2)") (class "Default")
      (node (ref "R15") (pin "2") (pinfunction "2_2") (pintype "passive"))
      (node (ref "R16") (pin "1") (pinfunction "1_1") (pintype "passive"))
      (node (ref "U$8") (pin "+") (pinfunction "+_+") (pintype "bidirectional"))
    )
    (net (code "54") (name "Net-(R17-1)") (class "Default")
      (node (ref "R17") (pin "P$1") (pinfunction "1_P$1") (pintype "passive"))
      (node (ref "U$9") (pin "DRAIN") (pinfunction "DRAIN_DRAIN") (pintype "bidirectional"))
    )
    (net (code "55") (name "Net-(R17-2)") (class "Default")
      (node (ref "C5") (pin "+") (pinfunction "+_+") (pintype "bidirectional"))
      (node (ref "C7") (pin "-") (pinfunction "-_-") (pintype "bidirectional"))
      (node (ref "D4") (pin "C") (pinfunction "C_C") (pintype "passive"))
      (node (ref "R13") (pin "2") (pinfunction "2_2") (pintype "passive"))
      (node (ref "R15") (pin "1") (pinfunction "1_1") (pintype "passive"))
      (node (ref "R17") (pin "P$2") (pinfunction "2_P$2") (pintype "passive"))
      (node (ref "R20") (pin "1") (pinfunction "1_1") (pintype "passive"))
      (node (ref "U$10") (pin "IN-") (pinfunction "IN-_IN-") (pintype "bidirectional"))
      (node (ref "U$11") (pin "-") (pinfunction "-_-") (pintype "bidirectional"))
      (node (ref "U$11") (pin "FB") (pinfunction "FB_FB") (pintype "bidirectional"))
      (node (ref "U$12") (pin "SOURCE") (pinfunction "SOURCE_SOURCE") (pintype "bidirectional"))
      (node (ref "U$7") (pin "IN+") (pinfunction "IN+_IN+") (pintype "bidirectional"))
    )
    (net (code "56") (name "Net-(R19-Pad1)") (class "Default")
      (node (ref "R19") (pin "1") (pinfunction "1_1") (pintype "passive"))
      (node (ref "R20") (pin "2") (pinfunction "2_2") (pintype "passive"))
      (node (ref "U$10") (pin "V+") (pinfunction "V+_V+") (pintype "bidirectional"))
    )
    (net (code "57") (name "Net-(R21-Pad2)") (class "Default")
      (node (ref "R21") (pin "2") (pinfunction "2_2") (pintype "passive"))
      (node (ref "R22") (pin "1") (pinfunction "1_1") (pintype "passive"))
      (node (ref "U$11") (pin "+") (pinfunction "+_+") (pintype "bidirectional"))
    )
    (net (code "58") (name "Net-(R23-1)") (class "Default")
      (node (ref "R23") (pin "P$1") (pinfunction "1_P$1") (pintype "passive"))
      (node (ref "U$12") (pin "DRAIN") (pinfunction "DRAIN_DRAIN") (pintype "bidirectional"))
    )
    (net (code "59") (name "Net-(R23-2)") (class "Default")
      (node (ref "C7") (pin "+") (pinfunction "+_+") (pintype "bidirectional"))
      (node (ref "C9") (pin "-") (pinfunction "-_-") (pintype "bidirectional"))
      (node (ref "D5") (pin "C") (pinfunction "C_C") (pintype "passive"))
      (node (ref "R19") (pin "2") (pinfunction "2_2") (pintype "passive"))
      (node (ref "R21") (pin "1") (pinfunction "1_1") (pintype "passive"))
      (node (ref "R23") (pin "P$2") (pinfunction "2_P$2") (pintype "passive"))
      (node (ref "R26") (pin "1") (pinfunction "1_1") (pintype "passive"))
      (node (ref "U$10") (pin "IN+") (pinfunction "IN+_IN+") (pintype "bidirectional"))
      (node (ref "U$13") (pin "IN-") (pinfunction "IN-_IN-") (pintype "bidirectional"))
      (node (ref "U$14") (pin "-") (pinfunction "-_-") (pintype "bidirectional"))
      (node (ref "U$14") (pin "FB") (pinfunction "FB_FB") (pintype "bidirectional"))
      (node (ref "U$15") (pin "SOURCE") (pinfunction "SOURCE_SOURCE") (pintype "bidirectional"))
    )
    (net (code "60") (name "Net-(R25-Pad1)") (class "Default")
      (node (ref "R25") (pin "1") (pinfunction "1_1") (pintype "passive"))
      (node (ref "R26") (pin "2") (pinfunction "2_2") (pintype "passive"))
      (node (ref "U$13") (pin "V+") (pinfunction "V+_V+") (pintype "bidirectional"))
    )
    (net (code "61") (name "Net-(R27-Pad2)") (class "Default")
      (node (ref "R27") (pin "2") (pinfunction "2_2") (pintype "passive"))
      (node (ref "R28") (pin "1") (pinfunction "1_1") (pintype "passive"))
      (node (ref "U$14") (pin "+") (pinfunction "+_+") (pintype "bidirectional"))
    )
    (net (code "62") (name "Net-(R29-1)") (class "Default")
      (node (ref "R29") (pin "P$1") (pinfunction "1_P$1") (pintype "passive"))
      (node (ref "U$15") (pin "DRAIN") (pinfunction "DRAIN_DRAIN") (pintype "bidirectional"))
    )
    (net (code "63") (name "Net-(R29-2)") (class "Default")
      (node (ref "C11") (pin "-") (pinfunction "-_-") (pintype "bidirectional"))
      (node (ref "C9") (pin "+") (pinfunction "+_+") (pintype "bidirectional"))
      (node (ref "D6") (pin "C") (pinfunction "C_C") (pintype "passive"))
      (node (ref "R25") (pin "2") (pinfunction "2_2") (pintype "passive"))
      (node (ref "R27") (pin "1") (pinfunction "1_1") (pintype "passive"))
      (node (ref "R29") (pin "P$2") (pinfunction "2_P$2") (pintype "passive"))
      (node (ref "R32") (pin "1") (pinfunction "1_1") (pintype "passive"))
      (node (ref "U$13") (pin "IN+") (pinfunction "IN+_IN+") (pintype "bidirectional"))
      (node (ref "U$16") (pin "IN-") (pinfunction "IN-_IN-") (pintype "bidirectional"))
      (node (ref "U$17") (pin "-") (pinfunction "-_-") (pintype "bidirectional"))
      (node (ref "U$17") (pin "FB") (pinfunction "FB_FB") (pintype "bidirectional"))
      (node (ref "U$18") (pin "SOURCE") (pinfunction "SOURCE_SOURCE") (pintype "bidirectional"))
    )
    (net (code "64") (name "Net-(R31-Pad1)") (class "Default")
      (node (ref "R31") (pin "1") (pinfunction "1_1") (pintype "passive"))
      (node (ref "R32") (pin "2") (pinfunction "2_2") (pintype "passive"))
      (node (ref "U$16") (pin "V+") (pinfunction "V+_V+") (pintype "bidirectional"))
    )
    (net (code "65") (name "Net-(R33-Pad2)") (class "Default")
      (node (ref "R33") (pin "2") (pinfunction "2_2") (pintype "passive"))
      (node (ref "R34") (pin "1") (pinfunction "1_1") (pintype "passive"))
      (node (ref "U$17") (pin "+") (pinfunction "+_+") (pintype "bidirectional"))
    )
    (net (code "66") (name "Net-(R35-1)") (class "Default")
      (node (ref "R35") (pin "P$1") (pinfunction "1_P$1") (pintype "passive"))
      (node (ref "U$18") (pin "DRAIN") (pinfunction "DRAIN_DRAIN") (pintype "bidirectional"))
    )
    (net (code "67") (name "Net-(R35-2)") (class "Default")
      (node (ref "C11") (pin "+") (pinfunction "+_+") (pintype "bidirectional"))
      (node (ref "C13") (pin "-") (pinfunction "-_-") (pintype "bidirectional"))
      (node (ref "D7") (pin "C") (pinfunction "C_C") (pintype "passive"))
      (node (ref "R31") (pin "2") (pinfunction "2_2") (pintype "passive"))
      (node (ref "R33") (pin "1") (pinfunction "1_1") (pintype "passive"))
      (node (ref "R35") (pin "P$2") (pinfunction "2_P$2") (pintype "passive"))
      (node (ref "R38") (pin "1") (pinfunction "1_1") (pintype "passive"))
      (node (ref "U$16") (pin "IN+") (pinfunction "IN+_IN+") (pintype "bidirectional"))
      (node (ref "U$19") (pin "IN-") (pinfunction "IN-_IN-") (pintype "bidirectional"))
      (node (ref "U$20") (pin "-") (pinfunction "-_-") (pintype "bidirectional"))
      (node (ref "U$20") (pin "FB") (pinfunction "FB_FB") (pintype "bidirectional"))
      (node (ref "U$21") (pin "SOURCE") (pinfunction "SOURCE_SOURCE") (pintype "bidirectional"))
    )
    (net (code "68") (name "Net-(R37-Pad1)") (class "Default")
      (node (ref "R37") (pin "1") (pinfunction "1_1") (pintype "passive"))
      (node (ref "R38") (pin "2") (pinfunction "2_2") (pintype "passive"))
      (node (ref "U$19") (pin "V+") (pinfunction "V+_V+") (pintype "bidirectional"))
    )
    (net (code "69") (name "Net-(R39-Pad2)") (class "Default")
      (node (ref "R39") (pin "2") (pinfunction "2_2") (pintype "passive"))
      (node (ref "R40") (pin "1") (pinfunction "1_1") (pintype "passive"))
      (node (ref "U$20") (pin "+") (pinfunction "+_+") (pintype "bidirectional"))
    )
    (net (code "70") (name "Net-(R41-1)") (class "Default")
      (node (ref "R41") (pin "P$1") (pinfunction "1_P$1") (pintype "passive"))
      (node (ref "U$21") (pin "DRAIN") (pinfunction "DRAIN_DRAIN") (pintype "bidirectional"))
    )
    (net (code "71") (name "Net-(R41-2)") (class "Default")
      (node (ref "C13") (pin "+") (pinfunction "+_+") (pintype "bidirectional"))
      (node (ref "C15") (pin "-") (pinfunction "-_-") (pintype "bidirectional"))
      (node (ref "D8") (pin "C") (pinfunction "C_C") (pintype "passive"))
      (node (ref "R37") (pin "2") (pinfunction "2_2") (pintype "passive"))
      (node (ref "R39") (pin "1") (pinfunction "1_1") (pintype "passive"))
      (node (ref "R41") (pin "P$2") (pinfunction "2_P$2") (pintype "passive"))
      (node (ref "R44") (pin "1") (pinfunction "1_1") (pintype "passive"))
      (node (ref "U$19") (pin "IN+") (pinfunction "IN+_IN+") (pintype "bidirectional"))
      (node (ref "U$22") (pin "IN-") (pinfunction "IN-_IN-") (pintype "bidirectional"))
      (node (ref "U$23") (pin "-") (pinfunction "-_-") (pintype "bidirectional"))
      (node (ref "U$23") (pin "FB") (pinfunction "FB_FB") (pintype "bidirectional"))
      (node (ref "U$24") (pin "SOURCE") (pinfunction "SOURCE_SOURCE") (pintype "bidirectional"))
    )
    (net (code "72") (name "Net-(R43-Pad1)") (class "Default")
      (node (ref "R43") (pin "1") (pinfunction "1_1") (pintype "passive"))
      (node (ref "R44") (pin "2") (pinfunction "2_2") (pintype "passive"))
      (node (ref "U$22") (pin "V+") (pinfunction "V+_V+") (pintype "bidirectional"))
    )
    (net (code "73") (name "Net-(R45-Pad2)") (class "Default")
      (node (ref "R45") (pin "2") (pinfunction "2_2") (pintype "passive"))
      (node (ref "R46") (pin "1") (pinfunction "1_1") (pintype "passive"))
      (node (ref "U$23") (pin "+") (pinfunction "+_+") (pintype "bidirectional"))
    )
    (net (code "74") (name "Net-(R47-1)") (class "Default")
      (node (ref "R47") (pin "P$1") (pinfunction "1_P$1") (pintype "passive"))
      (node (ref "U$24") (pin "DRAIN") (pinfunction "DRAIN_DRAIN") (pintype "bidirectional"))
    )
    (net (code "75") (name "Net-(R47-2)") (class "Default")
      (node (ref "C15") (pin "+") (pinfunction "+_+") (pintype "bidirectional"))
      (node (ref "C17") (pin "-") (pinfunction "-_-") (pintype "bidirectional"))
      (node (ref "D9") (pin "C") (pinfunction "C_C") (pintype "passive"))
      (node (ref "R43") (pin "2") (pinfunction "2_2") (pintype "passive"))
      (node (ref "R45") (pin "1") (pinfunction "1_1") (pintype "passive"))
      (node (ref "R47") (pin "P$2") (pinfunction "2_P$2") (pintype "passive"))
      (node (ref "R50") (pin "1") (pinfunction "1_1") (pintype "passive"))
      (node (ref "U$22") (pin "IN+") (pinfunction "IN+_IN+") (pintype "bidirectional"))
      (node (ref "U$25") (pin "IN-") (pinfunction "IN-_IN-") (pintype "bidirectional"))
      (node (ref "U$26") (pin "-") (pinfunction "-_-") (pintype "bidirectional"))
      (node (ref "U$26") (pin "FB") (pinfunction "FB_FB") (pintype "bidirectional"))
      (node (ref "U$27") (pin "SOURCE") (pinfunction "SOURCE_SOURCE") (pintype "bidirectional"))
    )
    (net (code "76") (name "Net-(R49-Pad1)") (class "Default")
      (node (ref "R49") (pin "1") (pinfunction "1_1") (pintype "passive"))
      (node (ref "R50") (pin "2") (pinfunction "2_2") (pintype "passive"))
      (node (ref "U$25") (pin "V+") (pinfunction "V+_V+") (pintype "bidirectional"))
    )
    (net (code "77") (name "Net-(R51-Pad2)") (class "Default")
      (node (ref "R51") (pin "2") (pinfunction "2_2") (pintype "passive"))
      (node (ref "R52") (pin "1") (pinfunction "1_1") (pintype "passive"))
      (node (ref "U$26") (pin "+") (pinfunction "+_+") (pintype "bidirectional"))
    )
    (net (code "78") (name "Net-(R53-1)") (class "Default")
      (node (ref "R53") (pin "P$1") (pinfunction "1_P$1") (pintype "passive"))
      (node (ref "U$27") (pin "DRAIN") (pinfunction "DRAIN_DRAIN") (pintype "bidirectional"))
    )
    (net (code "79") (name "Net-(R62-Pad2)") (class "Default")
      (node (ref "R62") (pin "2") (pinfunction "2_2") (pintype "passive"))
      (node (ref "R64") (pin "1") (pinfunction "1_1") (pintype "passive"))
      (node (ref "U$38") (pin "13") (pinfunction "13_13") (pintype "bidirectional"))
    )
    (net (code "80") (name "Net-(R63-Pad2)") (class "Default")
      (node (ref "R63") (pin "2") (pinfunction "2_2") (pintype "passive"))
      (node (ref "U$38") (pin "12") (pinfunction "12_12") (pintype "bidirectional"))
    )
    (net (code "81") (name "Net-(R65-Pad2)") (class "Default")
      (node (ref "R65") (pin "2") (pinfunction "2_2") (pintype "passive"))
      (node (ref "U$38") (pin "11") (pinfunction "11_11") (pintype "bidirectional"))
    )
    (net (code "82") (name "Net-(U$35-A-7)") (class "Default")
      (node (ref "R55") (pin "2") (pinfunction "2_2") (pintype "passive"))
      (node (ref "U$35") (pin "7") (pinfunction "A-7_7") (pintype "bidirectional"))
      (node (ref "U$36") (pin "7") (pinfunction "A-7_7") (pintype "bidirectional"))
      (node (ref "U$37") (pin "7") (pinfunction "A-7_7") (pintype "bidirectional"))
    )
    (net (code "83") (name "Net-(U$35-B-6)") (class "Default")
      (node (ref "R56") (pin "2") (pinfunction "2_2") (pintype "passive"))
      (node (ref "U$35") (pin "6") (pinfunction "B-6_6") (pintype "bidirectional"))
      (node (ref "U$36") (pin "6") (pinfunction "B-6_6") (pintype "bidirectional"))
      (node (ref "U$37") (pin "6") (pinfunction "B-6_6") (pintype "bidirectional"))
    )
    (net (code "84") (name "Net-(U$35-C-4)") (class "Default")
      (node (ref "R57") (pin "2") (pinfunction "2_2") (pintype "passive"))
      (node (ref "U$35") (pin "4") (pinfunction "C-4_4") (pintype "bidirectional"))
      (node (ref "U$36") (pin "4") (pinfunction "C-4_4") (pintype "bidirectional"))
      (node (ref "U$37") (pin "4") (pinfunction "C-4_4") (pintype "bidirectional"))
    )
    (net (code "85") (name "Net-(U$35-D-2)") (class "Default")
      (node (ref "R58") (pin "2") (pinfunction "2_2") (pintype "passive"))
      (node (ref "U$35") (pin "2") (pinfunction "D-2_2") (pintype "bidirectional"))
      (node (ref "U$36") (pin "2") (pinfunction "D-2_2") (pintype "bidirectional"))
      (node (ref "U$37") (pin "2") (pinfunction "D-2_2") (pintype "bidirectional"))
    )
    (net (code "86") (name "Net-(U$35-E-1)") (class "Default")
      (node (ref "R59") (pin "2") (pinfunction "2_2") (pintype "passive"))
      (node (ref "U$35") (pin "1") (pinfunction "E-1_1") (pintype "bidirectional"))
      (node (ref "U$36") (pin "1") (pinfunction "E-1_1") (pintype "bidirectional"))
      (node (ref "U$37") (pin "1") (pinfunction "E-1_1") (pintype "bidirectional"))
    )
    (net (code "87") (name "Net-(U$35-F-9)") (class "Default")
      (node (ref "R60") (pin "2") (pinfunction "2_2") (pintype "passive"))
      (node (ref "U$35") (pin "9") (pinfunction "F-9_9") (pintype "bidirectional"))
      (node (ref "U$36") (pin "9") (pinfunction "F-9_9") (pintype "bidirectional"))
      (node (ref "U$37") (pin "9") (pinfunction "F-9_9") (pintype "bidirectional"))
    )
    (net (code "88") (name "Net-(U$35-G-10)") (class "Default")
      (node (ref "R61") (pin "2") (pinfunction "2_2") (pintype "passive"))
      (node (ref "U$35") (pin "10") (pinfunction "G-10_10") (pintype "bidirectional"))
      (node (ref "U$36") (pin "10") (pinfunction "G-10_10") (pintype "bidirectional"))
      (node (ref "U$37") (pin "10") (pinfunction "G-10_10") (pintype "bidirectional"))
    )
    (net (code "89") (name "Net-(U$35-G1-3)") (class "Default")
      (node (ref "U$35") (pin "3") (pinfunction "G1-3_3") (pintype "bidirectional"))
      (node (ref "U$35") (pin "8") (pinfunction "G2-8_8") (pintype "bidirectional"))
      (node (ref "U$40") (pin "P$1") (pinfunction "C_P$1") (pintype "bidirectional"))
    )
    (net (code "90") (name "Net-(U$36-G1-3)") (class "Default")
      (node (ref "U$36") (pin "3") (pinfunction "G1-3_3") (pintype "bidirectional"))
      (node (ref "U$36") (pin "8") (pinfunction "G2-8_8") (pintype "bidirectional"))
      (node (ref "U$42") (pin "P$1") (pinfunction "C_P$1") (pintype "bidirectional"))
    )
    (net (code "91") (name "Net-(U$37-DP-5)") (class "Default")
      (node (ref "R62") (pin "1") (pinfunction "1_1") (pintype "passive"))
      (node (ref "U$37") (pin "5") (pinfunction "DP-5_5") (pintype "bidirectional"))
    )
    (net (code "92") (name "Net-(U$37-G1-3)") (class "Default")
      (node (ref "U$37") (pin "3") (pinfunction "G1-3_3") (pintype "bidirectional"))
      (node (ref "U$37") (pin "8") (pinfunction "G2-8_8") (pintype "bidirectional"))
      (node (ref "U$41") (pin "P$1") (pinfunction "C_P$1") (pintype "bidirectional"))
    )
    (net (code "93") (name "Net-(U$40-B)") (class "Default")
      (node (ref "R63") (pin "1") (pinfunction "1_1") (pintype "passive"))
      (node (ref "U$40") (pin "P$3") (pinfunction "B_P$3") (pintype "bidirectional"))
    )
    (net (code "94") (name "Net-(U$41-B)") (class "Default")
      (node (ref "R64") (pin "2") (pinfunction "2_2") (pintype "passive"))
      (node (ref "U$41") (pin "P$3") (pinfunction "B_P$3") (pintype "bidirectional"))
    )
    (net (code "95") (name "Net-(U$42-B)") (class "Default")
      (node (ref "R65") (pin "1") (pinfunction "1_1") (pintype "passive"))
      (node (ref "U$42") (pin "P$3") (pinfunction "B_P$3") (pintype "bidirectional"))
    )
    (net (code "96") (name "Net-(VR1-CW)") (class "Default")
      (node (ref "C19") (pin "1") (pinfunction "1_1") (pintype "passive"))
      (node (ref "D10") (pin "C") (pinfunction "C_C") (pintype "passive"))
      (node (ref "R66") (pin "2") (pinfunction "2_2") (pintype "passive"))
      (node (ref "U$38") (pin "3") (pinfunction "3_3") (pintype "bidirectional"))
      (node (ref "VR1") (pin "1") (pinfunction "CW_1") (pintype "passive"))
    )
    (net (code "97") (name "SW") (class "Default")
      (node (ref "3.3V_BUCK") (pin "1") (pinfunction "SW_1") (pintype "bidirectional"))
      (node (ref "C20") (pin "2") (pinfunction "2_2") (pintype "passive"))
      (node (ref "D11") (pin "C") (pinfunction "C_C") (pintype "passive"))
      (node (ref "U$39") (pin "P$1") (pinfunction "P$1_P$1") (pintype "bidirectional"))
    )
    (net (code "98") (name "VCC") (class "Default")
      (node (ref "3.3V_BUCK") (pin "7") (pinfunction "VIN_7") (pintype "bidirectional"))
      (node (ref "C17") (pin "+") (pinfunction "+_+") (pintype "bidirectional"))
      (node (ref "C23") (pin "1") (pinfunction "1_1") (pintype "passive"))
      (node (ref "CHARGE") (pin "1") (pinfunction "VCC_1") (pintype "bidirectional"))
      (node (ref "MTR") (pin "1") (pinfunction "VCC_1") (pintype "bidirectional"))
      (node (ref "R49") (pin "2") (pinfunction "2_2") (pintype "passive"))
      (node (ref "R51") (pin "1") (pinfunction "1_1") (pintype "passive"))
      (node (ref "R53") (pin "P$2") (pinfunction "2_P$2") (pintype "passive"))
      (node (ref "R66") (pin "1") (pinfunction "1_1") (pintype "passive"))
      (node (ref "R68") (pin "2") (pinfunction "2_2") (pintype "passive"))
      (node (ref "U$25") (pin "IN+") (pinfunction "IN+_IN+") (pintype "bidirectional"))
    )
    (net (code "99") (name "unconnected-(U$35-DP-5-Pad5)") (class "Default")
      (node (ref "U$35") (pin "5") (pinfunction "DP-5_5") (pintype "bidirectional"))
    )
    (net (code "100") (name "unconnected-(U$36-DP-5-Pad5)") (class "Default")
      (node (ref "U$36") (pin "5") (pinfunction "DP-5_5") (pintype "bidirectional"))
    )
    (net (code "101") (name "unconnected-(U$38-Pad4)") (class "Default")
      (node (ref "U$38") (pin "4") (pinfunction "4_4") (pintype "bidirectional"))
    )
  )
)
